# LiPolyRGB.net
KiCad netlist of a schematic drawn in EAGLE
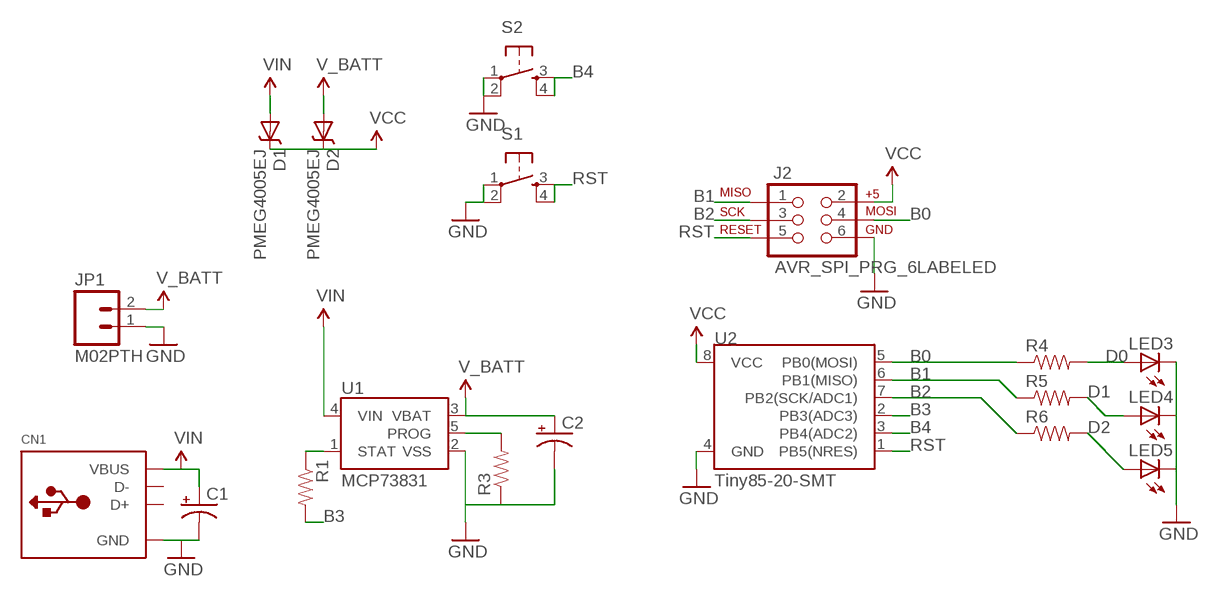
[diagram p0: schematic, sheet 1]

(export (version "E")
  (design (tool "Eeschema 10.0.6"))
  (components
    (comp (ref "C1")
      (value "CAP_POL1206")
      (footprint "eagle-import:EIA3216")
      (libsource (lib "eagle-import") (part "CAP_POL1206"))
    )
    (comp (ref "C2")
      (value "CAP_POL1206")
      (footprint "eagle-import:EIA3216")
      (libsource (lib "eagle-import") (part "CAP_POL1206"))
    )
    (comp (ref "CN1")
      (value "USB_TYPEAPCB")
      (footprint "eagle-import:USBA_PCB")
      (libsource (lib "eagle-import") (part "USB_TYPEAPCB"))
    )
    (comp (ref "D1")
      (value "PMEG4005EJ")
      (footprint "eagle-import:SOD-323")
      (libsource (lib "eagle-import") (part "DIODE-SCHOTTKY-PMEG4005EJ"))
    )
    (comp (ref "D2")
      (value "PMEG4005EJ")
      (footprint "eagle-import:SOD-323")
      (libsource (lib "eagle-import") (part "DIODE-SCHOTTKY-PMEG4005EJ"))
    )
    (comp (ref "J2")
      (value "AVR_SPI_PRG_6LABELED")
      (footprint "eagle-import:2X3-NS")
      (libsource (lib "eagle-import") (part "AVR_SPI_PRG_6LABELED"))
    )
    (comp (ref "JP1")
      (value "M02PTH")
      (footprint "eagle-import:1X02")
      (libsource (lib "eagle-import") (part "M02PTH"))
    )
    (comp (ref "LED3")
      (value "LEDOVAL_EDGE")
      (footprint "eagle-import:LED-OVAL-EDGE")
      (libsource (lib "eagle-import") (part "LEDOVAL_EDGE"))
    )
    (comp (ref "LED4")
      (value "LEDOVAL_EDGE")
      (footprint "eagle-import:LED-OVAL-EDGE")
      (libsource (lib "eagle-import") (part "LEDOVAL_EDGE"))
    )
    (comp (ref "LED5")
      (value "LEDOVAL_EDGE")
      (footprint "eagle-import:LED-OVAL-EDGE")
      (libsource (lib "eagle-import") (part "LEDOVAL_EDGE"))
    )
    (comp (ref "R1")
      (value "RESISTOR0805-RES")
      (footprint "eagle-import:0805")
      (libsource (lib "eagle-import") (part "RESISTOR0805-RES"))
    )
    (comp (ref "R3")
      (value "RESISTOR0805-RES")
      (footprint "eagle-import:0805")
      (libsource (lib "eagle-import") (part "RESISTOR0805-RES"))
    )
    (comp (ref "R4")
      (value "RESISTOR0805-RES")
      (footprint "eagle-import:0805")
      (libsource (lib "eagle-import") (part "RESISTOR0805-RES"))
    )
    (comp (ref "R5")
      (value "RESISTOR0805-RES")
      (footprint "eagle-import:0805")
      (libsource (lib "eagle-import") (part "RESISTOR0805-RES"))
    )
    (comp (ref "R6")
      (value "RESISTOR0805-RES")
      (footprint "eagle-import:0805")
      (libsource (lib "eagle-import") (part "RESISTOR0805-RES"))
    )
    (comp (ref "S1")
      (value "TAC_SWITCHSMD")
      (footprint "eagle-import:TACTILE-SWITCH-SMD")
      (libsource (lib "eagle-import") (part "TAC_SWITCHSMD"))
    )
    (comp (ref "S2")
      (value "TAC_SWITCHSMD")
      (footprint "eagle-import:TACTILE-SWITCH-SMD")
      (libsource (lib "eagle-import") (part "TAC_SWITCHSMD"))
    )
    (comp (ref "U1")
      (value "MCP73831")
      (footprint "eagle-import:SOT23-5")
      (libsource (lib "eagle-import") (part "MCP73831"))
    )
    (comp (ref "U2")
      (value "Tiny85-20-SMT")
      (footprint "eagle-import:SO08-EIAJ")
      (libsource (lib "eagle-import") (part "ATTINY45TINY85-20-SMT"))
    )
  )
  (nets
    (net (code "1") (name "/B0") (class "Default")
      (node (ref "J2") (pin "4") (pinfunction "4_4") (pintype "passive"))
      (node (ref "R4") (pin "1") (pinfunction "1_1") (pintype "passive"))
      (node (ref "U2") (pin "5") (pinfunction "PB0(MOSI)_5") (pintype "bidirectional"))
    )
    (net (code "2") (name "/B1") (class "Default")
      (node (ref "J2") (pin "1") (pinfunction "1_1") (pintype "passive"))
      (node (ref "R5") (pin "1") (pinfunction "1_1") (pintype "passive"))
      (node (ref "U2") (pin "6") (pinfunction "PB1(MISO)_6") (pintype "bidirectional"))
    )
    (net (code "3") (name "/B2") (class "Default")
      (node (ref "J2") (pin "3") (pinfunction "3_3") (pintype "passive"))
      (node (ref "R6") (pin "1") (pinfunction "1_1") (pintype "passive"))
      (node (ref "U2") (pin "7") (pinfunction "PB2(SCK/ADC1)_7") (pintype "bidirectional"))
    )
    (net (code "4") (name "/B3") (class "Default")
      (node (ref "R1") (pin "2") (pinfunction "2_2") (pintype "passive"))
      (node (ref "U2") (pin "2") (pinfunction "PB3(ADC3)_2") (pintype "bidirectional"))
    )
    (net (code "5") (name "/B4") (class "Default")
      (node (ref "S2") (pin "3") (pinfunction "3_3") (pintype "passive"))
      (node (ref "S2") (pin "4") (pinfunction "4_4") (pintype "passive"))
      (node (ref "U2") (pin "3") (pinfunction "PB4(ADC2)_3") (pintype "bidirectional"))
    )
    (net (code "6") (name "/D0") (class "Default")
      (node (ref "LED3") (pin "ANODE") (pinfunction "A_ANODE") (pintype "passive"))
      (node (ref "R4") (pin "2") (pinfunction "2_2") (pintype "passive"))
    )
    (net (code "7") (name "/D1") (class "Default")
      (node (ref "LED4") (pin "ANODE") (pinfunction "A_ANODE") (pintype "passive"))
      (node (ref "R5") (pin "2") (pinfunction "2_2") (pintype "passive"))
    )
    (net (code "8") (name "/D2") (class "Default")
      (node (ref "LED5") (pin "ANODE") (pinfunction "A_ANODE") (pintype "passive"))
      (node (ref "R6") (pin "2") (pinfunction "2_2") (pintype "passive"))
    )
    (net (code "9") (name "/RST") (class "Default")
      (node (ref "J2") (pin "5") (pinfunction "5_5") (pintype "passive"))
      (node (ref "S1") (pin "3") (pinfunction "3_3") (pintype "passive"))
      (node (ref "S1") (pin "4") (pinfunction "4_4") (pintype "passive"))
      (node (ref "U2") (pin "1") (pinfunction "PB5(NRES)_1") (pintype "bidirectional"))
    )
    (net (code "10") (name "GND") (class "Default")
      (node (ref "C1") (pin "C") (pinfunction "-_C") (pintype "passive"))
      (node (ref "C2") (pin "C") (pinfunction "-_C") (pintype "passive"))
      (node (ref "CN1") (pin "GND") (pinfunction "GND_GND") (pintype "power_in"))
      (node (ref "J2") (pin "6") (pinfunction "6_6") (pintype "passive"))
      (node (ref "JP1") (pin "1") (pinfunction "1_1") (pintype "passive"))
      (node (ref "LED3") (pin "CATHODE") (pinfunction "C_CATHODE") (pintype "passive"))
      (node (ref "LED4") (pin "CATHODE") (pinfunction "C_CATHODE") (pintype "passive"))
      (node (ref "LED5") (pin "CATHODE") (pinfunction "C_CATHODE") (pintype "passive"))
      (node (ref "R3") (pin "1") (pinfunction "1_1") (pintype "passive"))
      (node (ref "S1") (pin "1") (pinfunction "1_1") (pintype "passive"))
      (node (ref "S1") (pin "2") (pinfunction "2_2") (pintype "passive"))
      (node (ref "S2") (pin "1") (pinfunction "1_1") (pintype "passive"))
      (node (ref "S2") (pin "2") (pinfunction "2_2") (pintype "passive"))
      (node (ref "U1") (pin "2") (pinfunction "VSS_2") (pintype "power_in"))
      (node (ref "U2") (pin "4") (pinfunction "GND_4") (pintype "bidirectional"))
    )
    (net (code "11") (name "Net-(U1-PROG)") (class "Default")
      (node (ref "R3") (pin "2") (pinfunction "2_2") (pintype "passive"))
      (node (ref "U1") (pin "5") (pinfunction "PROG_5") (pintype "input"))
    )
    (net (code "12") (name "Net-(U1-STAT)") (class "Default")
      (node (ref "R1") (pin "1") (pinfunction "1_1") (pintype "passive"))
      (node (ref "U1") (pin "1") (pinfunction "STAT_1") (pintype "output"))
    )
    (net (code "13") (name "VCC") (class "Default")
      (node (ref "D1") (pin "C") (pinfunction "C_C") (pintype "passive"))
      (node (ref "D2") (pin "C") (pinfunction "C_C") (pintype "passive"))
      (node (ref "J2") (pin "2") (pinfunction "2_2") (pintype "passive"))
      (node (ref "U2") (pin "8") (pinfunction "VCC_8") (pintype "bidirectional"))
    )
    (net (code "14") (name "VIN") (class "Default")
      (node (ref "C1") (pin "A") (pinfunction "+_A") (pintype "passive"))
      (node (ref "CN1") (pin "VCC") (pinfunction "VBUS_VCC") (pintype "power_in"))
      (node (ref "D1") (pin "A") (pinfunction "A_A") (pintype "passive"))
      (node (ref "U1") (pin "4") (pinfunction "VIN_4") (pintype "power_in"))
    )
    (net (code "15") (name "V_BATT") (class "Default")
      (node (ref "C2") (pin "A") (pinfunction "+_A") (pintype "passive"))
      (node (ref "D2") (pin "A") (pinfunction "A_A") (pintype "passive"))
      (node (ref "JP1") (pin "2") (pinfunction "2_2") (pintype "passive"))
      (node (ref "U1") (pin "3") (pinfunction "VBAT_3") (pintype "power_in"))
    )
    (net (code "16") (name "unconnected-(CN1-D+-PadUSB_PLUS)") (class "Default")
      (node (ref "CN1") (pin "USB_PLUS") (pinfunction "D+_USB_PLUS") (pintype "bidirectional"))
    )
    (net (code "17") (name "unconnected-(CN1-D--PadUSB_NEG)") (class "Default")
      (node (ref "CN1") (pin "USB_NEG") (pinfunction "D-_USB_NEG") (pintype "bidirectional"))
    )
  )
)
